# RFSwitch_SKY13330-397LF.net
KiCad netlist of a schematic drawn in Altium Designer
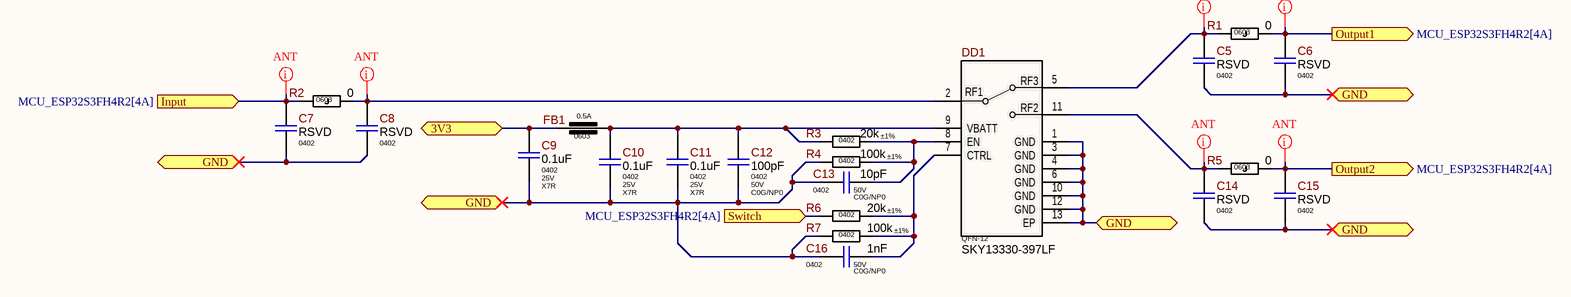
[diagram p0: RFSwitch_SKY13330-397LF.SchDoc]

(export (version "E")
  (design (tool "Eeschema 10.0.6"))
  (components
    (comp (ref "C5")
      (value "RSVD")
      (footprint "C_CERAMIC_0402_MED")
      (description "0402 Capacitor")
      (fields
        (field (name "PACKAGE") "0402")
        (field (name "PART NUMBER") "GENERIC-CAP-0402")
        (field (name "MANUFACTURER") "NONE")
      )
      (libsource (lib "EL.XXX.T01") (part "Capacitor-NonPolar"))
    )
    (comp (ref "C6")
      (value "RSVD")
      (footprint "C_CERAMIC_0402_MED")
      (description "0402 Capacitor")
      (fields
        (field (name "PACKAGE") "0402")
        (field (name "PART NUMBER") "GENERIC-CAP-0402")
        (field (name "MANUFACTURER") "NONE")
      )
      (libsource (lib "EL.XXX.T01") (part "Capacitor-NonPolar"))
    )
    (comp (ref "C7")
      (value "RSVD")
      (footprint "C_CERAMIC_0402_MED")
      (description "0402 Capacitor")
      (fields
        (field (name "PACKAGE") "0402")
        (field (name "PART NUMBER") "GENERIC-CAP-0402")
        (field (name "MANUFACTURER") "NONE")
      )
      (libsource (lib "EL.XXX.T01") (part "Capacitor-NonPolar"))
    )
    (comp (ref "C8")
      (value "RSVD")
      (footprint "C_CERAMIC_0402_MED")
      (description "0402 Capacitor")
      (fields
        (field (name "PACKAGE") "0402")
        (field (name "PART NUMBER") "GENERIC-CAP-0402")
        (field (name "MANUFACTURER") "NONE")
      )
      (libsource (lib "EL.XXX.T01") (part "Capacitor-NonPolar"))
    )
    (comp (ref "C9")
      (value "0.1uF")
      (footprint "C_CERAMIC_0402_MED")
      (description "100nF 25V X7R ±10% 0402 Ceramic Capacitor RoHS")
      (fields
        (field (name "PACKAGE") "0402")
        (field (name "VOLTAGE") "25V")
        (field (name "DIELECTRIC TYPE") "X7R")
        (field (name "PART NUMBER") "GRM155R71E104KE14D")
        (field (name "MANUFACTURER") "Murata Electronics")
      )
      (libsource (lib "EL.XXX.T01") (part "Capacitor-NonPolar"))
    )
    (comp (ref "C10")
      (value "0.1uF")
      (footprint "C_CERAMIC_0402_MED")
      (description "100nF 25V X7R ±10% 0402 Ceramic Capacitor RoHS")
      (fields
        (field (name "PACKAGE") "0402")
        (field (name "VOLTAGE") "25V")
        (field (name "DIELECTRIC TYPE") "X7R")
        (field (name "PART NUMBER") "GRM155R71E104KE14D")
        (field (name "MANUFACTURER") "Murata Electronics")
      )
      (libsource (lib "EL.XXX.T01") (part "Capacitor-NonPolar"))
    )
    (comp (ref "C11")
      (value "0.1uF")
      (footprint "C_CERAMIC_0402_MED")
      (description "100nF 25V X7R ±10% 0402 Ceramic Capacitor RoHS")
      (fields
        (field (name "PACKAGE") "0402")
        (field (name "VOLTAGE") "25V")
        (field (name "DIELECTRIC TYPE") "X7R")
        (field (name "PART NUMBER") "GRM155R71E104KE14D")
        (field (name "MANUFACTURER") "Murata Electronics")
      )
      (libsource (lib "EL.XXX.T01") (part "Capacitor-NonPolar"))
    )
    (comp (ref "C12")
      (value "100pF")
      (footprint "C_CERAMIC_0402_MED")
      (description "100pF 50V C0G ±5% 0402 Ceramic Capacitor RoHS")
      (fields
        (field (name "PACKAGE") "0402")
        (field (name "VOLTAGE") "50V")
        (field (name "DIELECTRIC TYPE") "C0G/NP0")
        (field (name "PART NUMBER") "CC0402JPNPO9BN101")
        (field (name "MANUFACTURER") "Yageo")
      )
      (libsource (lib "EL.XXX.T01") (part "Capacitor-NonPolar"))
    )
    (comp (ref "C13")
      (value "10pF")
      (footprint "C_CERAMIC_0402_MED")
      (description "10pF 50V C0G ±5% 0402 Ceramic Capacitor RoHS")
      (fields
        (field (name "PACKAGE") "0402")
        (field (name "VOLTAGE") "50V")
        (field (name "DIELECTRIC TYPE") "C0G/NP0")
        (field (name "PART NUMBER") "CL05C100JB5NNNC")
        (field (name "MANUFACTURER") "Samsung Electro-Mechanics")
      )
      (libsource (lib "EL.XXX.T01") (part "Capacitor-NonPolar"))
    )
    (comp (ref "C14")
      (value "RSVD")
      (footprint "C_CERAMIC_0402_MED")
      (description "0402 Capacitor")
      (fields
        (field (name "PACKAGE") "0402")
        (field (name "PART NUMBER") "GENERIC-CAP-0402")
        (field (name "MANUFACTURER") "NONE")
      )
      (libsource (lib "EL.XXX.T01") (part "Capacitor-NonPolar"))
    )
    (comp (ref "C15")
      (value "RSVD")
      (footprint "C_CERAMIC_0402_MED")
      (description "0402 Capacitor")
      (fields
        (field (name "PACKAGE") "0402")
        (field (name "PART NUMBER") "GENERIC-CAP-0402")
        (field (name "MANUFACTURER") "NONE")
      )
      (libsource (lib "EL.XXX.T01") (part "Capacitor-NonPolar"))
    )
    (comp (ref "C16")
      (value "1nF")
      (footprint "C_CERAMIC_0402_MED")
      (description "1nF 50V C0G ±5% 0402 Ceramic Capacitor RoHS")
      (fields
        (field (name "PACKAGE") "0402")
        (field (name "VOLTAGE") "50V")
        (field (name "DIELECTRIC TYPE") "C0G/NP0")
        (field (name "PART NUMBER") "GRM1555C1H102JA01D")
        (field (name "MANUFACTURER") "Murata Electronics")
      )
      (libsource (lib "EL.XXX.T01") (part "Capacitor-NonPolar"))
    )
    (comp (ref "DD1")
      (value "SKY13330-397LF")
      (footprint "QFN-12_SKY13330-397LF")
      (description "0.1GHz to 6.0GHz SPDT RF Switch, 0.35 dB @ 2.2 GHz Loss, 50Ohm, QFN-12 (2x2mm)")
      (fields
        (field (name "PACKAGE") "QFN-12")
        (field (name "PART NUMBER") "SKY13330-397LF")
        (field (name "MANUFACTURER") "Skyworks Solutions")
      )
      (libsource (lib "EL.XXX.T01") (part "SKY13330-397LF"))
    )
    (comp (ref "FB1")
      (value "BLM18HE152SN1D")
      (footprint "BLM18HxxxxSN1x_MED")
      (description "1.5 kOhms @ 100MHz 1 Signal Line Ferrite Bead 0603, 500mA 500mOhm")
      (fields
        (field (name "CURRENT") "0.5A")
        (field (name "PACKAGE") "0603")
        (field (name "TOLERANCE") "±25%")
        (field (name "MANUFACTURER") "Murata Electronics")
      )
      (libsource (lib "EL.XXX.T01") (part "Ferrite-Bead"))
    )
    (comp (ref "R1")
      (value "0")
      (footprint "R_ANY_CHIP_0603_MED")
      (description "0 Ohms Jumper, 1/10W 0603 Thick Film Resistor")
      (fields
        (field (name "PACKAGE") "0603")
        (field (name "PART NUMBER") "RC0603JR-070RL")
        (field (name "MANUFACTURER") "Yageo")
      )
      (libsource (lib "EL.XXX.T01") (part "Resistor-J"))
    )
    (comp (ref "R2")
      (value "0")
      (footprint "R_ANY_CHIP_0603_MED")
      (description "0 Ohms Jumper, 1/10W 0603 Thick Film Resistor")
      (fields
        (field (name "PACKAGE") "0603")
        (field (name "PART NUMBER") "RC0603JR-070RL")
        (field (name "MANUFACTURER") "Yageo")
      )
      (libsource (lib "EL.XXX.T01") (part "Resistor-J"))
    )
    (comp (ref "R3")
      (value "20k")
      (footprint "R_ANY_CHIP_0402_MED")
      (description "20 kOhms ±1% 1/16W 0402 Thick Film Resistor")
      (fields
        (field (name "TOLERANCE") "±1%")
        (field (name "PACKAGE") "0402")
        (field (name "PART NUMBER") "RC0402FR-0720KL")
        (field (name "MANUFACTURER") "Yageo")
      )
      (libsource (lib "EL.XXX.T01") (part "Resistor"))
    )
    (comp (ref "R4")
      (value "100k")
      (footprint "R_ANY_CHIP_0402_MED")
      (description "100 kOhms ±1% 1/16W 0402 Thick Film Resistor")
      (fields
        (field (name "TOLERANCE") "±1%")
        (field (name "PACKAGE") "0402")
        (field (name "PART NUMBER") "RC0402FR-07100KL")
        (field (name "MANUFACTURER") "Yageo")
      )
      (libsource (lib "EL.XXX.T01") (part "Resistor"))
    )
    (comp (ref "R5")
      (value "0")
      (footprint "R_ANY_CHIP_0603_MED")
      (description "0 Ohms Jumper, 1/10W 0603 Thick Film Resistor")
      (fields
        (field (name "PACKAGE") "0603")
        (field (name "PART NUMBER") "RC0603JR-070RL")
        (field (name "MANUFACTURER") "Yageo")
      )
      (libsource (lib "EL.XXX.T01") (part "Resistor-J"))
    )
    (comp (ref "R6")
      (value "20k")
      (footprint "R_ANY_CHIP_0402_MED")
      (description "20 kOhms ±1% 1/16W 0402 Thick Film Resistor")
      (fields
        (field (name "TOLERANCE") "±1%")
        (field (name "PACKAGE") "0402")
        (field (name "PART NUMBER") "RC0402FR-0720KL")
        (field (name "MANUFACTURER") "Yageo")
      )
      (libsource (lib "EL.XXX.T01") (part "Resistor"))
    )
    (comp (ref "R7")
      (value "100k")
      (footprint "R_ANY_CHIP_0402_MED")
      (description "100 kOhms ±1% 1/16W 0402 Thick Film Resistor")
      (fields
        (field (name "TOLERANCE") "±1%")
        (field (name "PACKAGE") "0402")
        (field (name "PART NUMBER") "RC0402FR-07100KL")
        (field (name "MANUFACTURER") "Yageo")
      )
      (libsource (lib "EL.XXX.T01") (part "Resistor"))
    )
  )
  (nets
    (net (code "1") (name "/3V3") (class "Default")
      (node (ref "C9") (pin "1") (pinfunction "1_1") (pintype "passive"))
      (node (ref "FB1") (pin "2") (pintype "passive"))
    )
    (net (code "2") (name "/GND") (class "Default")
      (node (ref "C10") (pin "2") (pinfunction "2_2") (pintype "passive"))
      (node (ref "C11") (pin "2") (pinfunction "2_2") (pintype "passive"))
      (node (ref "C12") (pin "1") (pinfunction "1_1") (pintype "passive"))
      (node (ref "C13") (pin "1") (pinfunction "1_1") (pintype "passive"))
      (node (ref "C14") (pin "2") (pinfunction "2_2") (pintype "passive"))
      (node (ref "C15") (pin "2") (pinfunction "2_2") (pintype "passive"))
      (node (ref "C16") (pin "1") (pinfunction "1_1") (pintype "passive"))
      (node (ref "C5") (pin "2") (pinfunction "2_2") (pintype "passive"))
      (node (ref "C6") (pin "2") (pinfunction "2_2") (pintype "passive"))
      (node (ref "C7") (pin "2") (pinfunction "2_2") (pintype "passive"))
      (node (ref "C8") (pin "2") (pinfunction "2_2") (pintype "passive"))
      (node (ref "C9") (pin "2") (pinfunction "2_2") (pintype "passive"))
      (node (ref "DD1") (pin "1") (pinfunction "GND_1") (pintype "passive"))
      (node (ref "DD1") (pin "10") (pinfunction "GND_10") (pintype "passive"))
      (node (ref "DD1") (pin "12") (pinfunction "GND_12") (pintype "passive"))
      (node (ref "DD1") (pin "13") (pinfunction "EP_13") (pintype "passive"))
      (node (ref "DD1") (pin "3") (pinfunction "GND_3") (pintype "passive"))
      (node (ref "DD1") (pin "4") (pinfunction "GND_4") (pintype "passive"))
      (node (ref "DD1") (pin "6") (pinfunction "GND_6") (pintype "passive"))
      (node (ref "R4") (pin "2") (pintype "passive"))
      (node (ref "R7") (pin "1") (pintype "passive"))
    )
    (net (code "3") (name "/Input") (class "Default")
      (node (ref "C7") (pin "1") (pinfunction "1_1") (pintype "passive"))
      (node (ref "R2") (pin "2") (pintype "passive"))
    )
    (net (code "4") (name "/Output1") (class "Default")
      (node (ref "C6") (pin "1") (pinfunction "1_1") (pintype "passive"))
      (node (ref "R1") (pin "1") (pintype "passive"))
    )
    (net (code "5") (name "/Output2") (class "Default")
      (node (ref "C15") (pin "1") (pinfunction "1_1") (pintype "passive"))
      (node (ref "R5") (pin "1") (pintype "passive"))
    )
    (net (code "6") (name "/Switch") (class "Default") (node (ref "R6") (pin "1") (pintype "passive")))
    (net (code "7") (name "Net-(C5-Pad1)") (class "Default")
      (node (ref "C5") (pin "1") (pinfunction "1_1") (pintype "passive"))
      (node (ref "DD1") (pin "5") (pintype "passive"))
      (node (ref "R1") (pin "2") (pintype "passive"))
    )
    (net (code "8") (name "Net-(C8-Pad1)") (class "Default")
      (node (ref "C8") (pin "1") (pinfunction "1_1") (pintype "passive"))
      (node (ref "DD1") (pin "2") (pintype "passive"))
      (node (ref "R2") (pin "1") (pintype "passive"))
    )
    (net (code "9") (name "Net-(C14-Pad1)") (class "Default")
      (node (ref "C14") (pin "1") (pinfunction "1_1") (pintype "passive"))
      (node (ref "DD1") (pin "11") (pintype "passive"))
      (node (ref "R5") (pin "2") (pintype "passive"))
    )
    (net (code "10") (name "Net-(DD1-CTRL)") (class "Default")
      (node (ref "C16") (pin "2") (pinfunction "2_2") (pintype "passive"))
      (node (ref "DD1") (pin "7") (pinfunction "CTRL_7") (pintype "passive"))
      (node (ref "R6") (pin "2") (pintype "passive"))
      (node (ref "R7") (pin "2") (pintype "passive"))
    )
    (net (code "11") (name "Net-(DD1-EN)") (class "Default")
      (node (ref "C13") (pin "2") (pinfunction "2_2") (pintype "passive"))
      (node (ref "DD1") (pin "8") (pinfunction "EN_8") (pintype "passive"))
      (node (ref "R3") (pin "2") (pintype "passive"))
      (node (ref "R4") (pin "1") (pintype "passive"))
    )
    (net (code "12") (name "Net-(DD1-VBATT)") (class "Default")
      (node (ref "C10") (pin "1") (pinfunction "1_1") (pintype "passive"))
      (node (ref "C11") (pin "1") (pinfunction "1_1") (pintype "passive"))
      (node (ref "C12") (pin "2") (pinfunction "2_2") (pintype "passive"))
      (node (ref "DD1") (pin "9") (pinfunction "VBATT_9") (pintype "passive"))
      (node (ref "FB1") (pin "1") (pintype "passive"))
      (node (ref "R3") (pin "1") (pintype "passive"))
    )
  )
)
